# Data_Logger_1.net
KiCad netlist of a schematic drawn in EAGLE
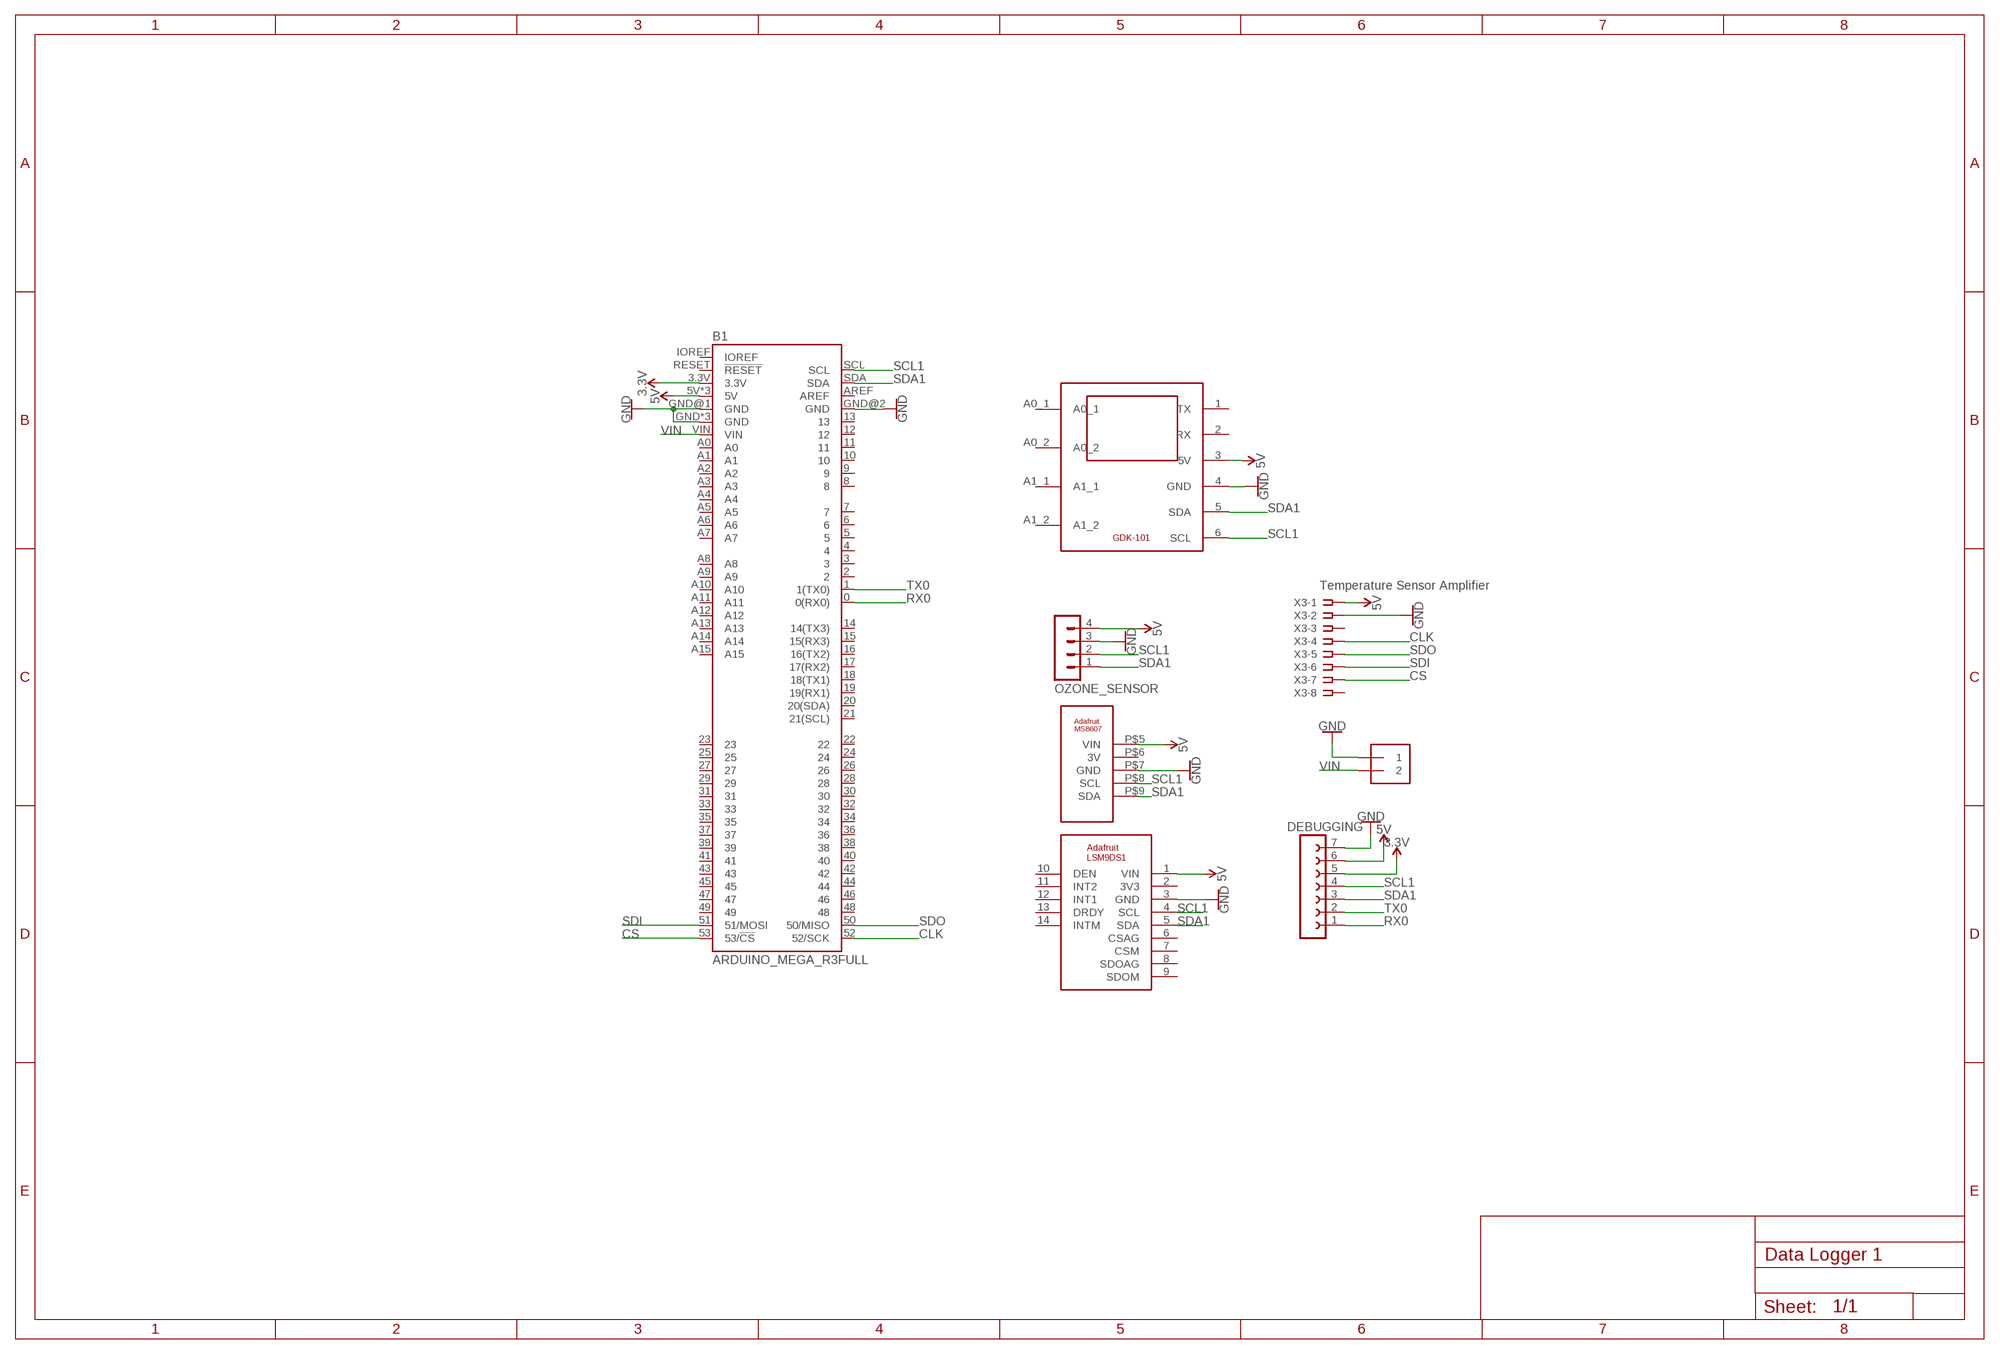
[diagram p0: schematic, sheet 1]

(export (version "E")
  (design (tool "Eeschema 10.0.6"))
  (components
    (comp (ref "B1")
      (value "ARDUINO_MEGA_R3FULL")
      (footprint "eagle-import:ARDUINO_MEGA_NO_SILK")
      (libsource (lib "eagle-import") (part "ARDUINO_MEGA_R3FULL"))
    )
    (comp (ref "DEBUGGING")
      (value "FE07-1")
      (footprint "eagle-import:FE07")
      (libsource (lib "eagle-import") (part "FE07-1"))
    )
    (comp (ref "OZONE_SENSOR")
      (value "OZONE_SENSOR")
      (footprint "eagle-import:MA04-1")
      (libsource (lib "eagle-import") (part "MA04-1"))
    )
    (comp (ref "POWER_7-12V")
      (value "1X2-3.5MM")
      (footprint "eagle-import:1X2-3.5MM")
      (libsource (lib "eagle-import") (part "1X2-3.5MM"))
    )
    (comp (ref "PRESSURE_SENSOR")
      (value "ADAFRUIT_MS8607")
      (footprint "eagle-import:ADAFRUIT_MS8607")
      (libsource (lib "eagle-import") (part "ADAFRUIT_MS8607"))
    )
    (comp (ref "U$1")
      (value "FTLAB_GAMMA_SENSOR_MODULETHROUGH_HOLE")
      (footprint "eagle-import:FTLAB_GAMMA_SENSOR_MODULE")
      (libsource (lib "eagle-import") (part "FTLAB_GAMMA_SENSOR_MODULETHROUGH_HOLE"))
    )
    (comp (ref "U$2")
      (value "ADAFRUIT_LSM9DS1")
      (footprint "eagle-import:ADAFRUIT_LSM9DS1")
      (libsource (lib "eagle-import") (part "ADAFRUIT_LSM9DS1"))
    )
    (comp (ref "X3")
      (value "Temperature Sensor Amplifier")
      (footprint "eagle-import:SSW-108-02-G-S")
      (fields (field (name "MF") "Samtec Inc.") (field (name "MPN") "SSW-108-02-G-S"))
      (libsource (lib "eagle-import") (part "SSW-108-02-G-S"))
    )
  )
  (nets
    (net (code "1") (name "/CLK") (class "Default")
      (node (ref "B1") (pin "52") (pinfunction "52/SCK_52") (pintype "bidirectional"))
      (node (ref "X3") (pin "4") (pinfunction "1_4") (pintype "passive"))
    )
    (net (code "2") (name "/CS") (class "Default")
      (node (ref "B1") (pin "53") (pinfunction "53/~{CS}_53") (pintype "bidirectional"))
      (node (ref "X3") (pin "7") (pinfunction "1_7") (pintype "passive"))
    )
    (net (code "3") (name "/RX0") (class "Default")
      (node (ref "B1") (pin "0") (pinfunction "0(RX0)_0") (pintype "bidirectional"))
      (node (ref "DEBUGGING") (pin "1") (pinfunction "1_1") (pintype "passive"))
    )
    (net (code "4") (name "/SCL1") (class "Default")
      (node (ref "B1") (pin "SCL") (pinfunction "SCL_SCL") (pintype "bidirectional"))
      (node (ref "DEBUGGING") (pin "4") (pinfunction "4_4") (pintype "passive"))
      (node (ref "OZONE_SENSOR") (pin "2") (pinfunction "2_2") (pintype "passive"))
      (node (ref "PRESSURE_SENSOR") (pin "P$8") (pinfunction "SCL_P$8") (pintype "bidirectional"))
      (node (ref "U$1") (pin "6") (pinfunction "SCL_6") (pintype "bidirectional"))
      (node (ref "U$2") (pin "4") (pinfunction "SCL_4") (pintype "bidirectional"))
    )
    (net (code "5") (name "/SDA1") (class "Default")
      (node (ref "B1") (pin "SDA") (pinfunction "SDA_SDA") (pintype "bidirectional"))
      (node (ref "DEBUGGING") (pin "3") (pinfunction "3_3") (pintype "passive"))
      (node (ref "OZONE_SENSOR") (pin "1") (pinfunction "1_1") (pintype "passive"))
      (node (ref "PRESSURE_SENSOR") (pin "P$9") (pinfunction "SDA_P$9") (pintype "bidirectional"))
      (node (ref "U$1") (pin "5") (pinfunction "SDA_5") (pintype "bidirectional"))
      (node (ref "U$2") (pin "5") (pinfunction "SDA_5") (pintype "bidirectional"))
    )
    (net (code "6") (name "/SDI") (class "Default")
      (node (ref "B1") (pin "51") (pinfunction "51/MOSI_51") (pintype "bidirectional"))
      (node (ref "X3") (pin "6") (pinfunction "1_6") (pintype "passive"))
    )
    (net (code "7") (name "/SDO") (class "Default")
      (node (ref "B1") (pin "50") (pinfunction "50/MISO_50") (pintype "bidirectional"))
      (node (ref "X3") (pin "5") (pinfunction "1_5") (pintype "passive"))
    )
    (net (code "8") (name "/TX0") (class "Default")
      (node (ref "B1") (pin "1") (pinfunction "1(TX0)_1") (pintype "bidirectional"))
      (node (ref "DEBUGGING") (pin "2") (pinfunction "2_2") (pintype "passive"))
    )
    (net (code "9") (name "/VIN") (class "Default")
      (node (ref "B1") (pin "VIN") (pinfunction "VIN_VIN") (pintype "bidirectional"))
      (node (ref "POWER_7-12V") (pin "2") (pinfunction "2_2") (pintype "passive"))
    )
    (net (code "10") (name "3.3V") (class "Default")
      (node (ref "B1") (pin "3.3V") (pinfunction "3.3V_3.3V") (pintype "bidirectional"))
      (node (ref "DEBUGGING") (pin "5") (pinfunction "5_5") (pintype "passive"))
    )
    (net (code "11") (name "5V") (class "Default")
      (node (ref "B1") (pin "5V") (pinfunction "5V_5V") (pintype "bidirectional"))
      (node (ref "B1") (pin "5V@1") (pinfunction "5V_5V@1") (pintype "bidirectional"))
      (node (ref "B1") (pin "5V@2") (pinfunction "5V_5V@2") (pintype "bidirectional"))
      (node (ref "DEBUGGING") (pin "6") (pinfunction "6_6") (pintype "passive"))
      (node (ref "OZONE_SENSOR") (pin "4") (pinfunction "4_4") (pintype "passive"))
      (node (ref "PRESSURE_SENSOR") (pin "P$5") (pinfunction "VIN_P$5") (pintype "bidirectional"))
      (node (ref "U$1") (pin "3") (pinfunction "5V_3") (pintype "bidirectional"))
      (node (ref "U$2") (pin "1") (pinfunction "VIN_1") (pintype "bidirectional"))
      (node (ref "X3") (pin "1") (pinfunction "1_1") (pintype "passive"))
    )
    (net (code "12") (name "GND") (class "Default")
      (node (ref "B1") (pin "GND") (pinfunction "GND_GND") (pintype "bidirectional"))
      (node (ref "B1") (pin "GND@1") (pinfunction "GND_GND@1") (pintype "bidirectional"))
      (node (ref "B1") (pin "GND@2") (pinfunction "GND_GND@2") (pintype "bidirectional"))
      (node (ref "B1") (pin "GND@3") (pinfunction "GND_GND@3") (pintype "bidirectional"))
      (node (ref "B1") (pin "GND@4") (pinfunction "GND_GND@4") (pintype "bidirectional"))
      (node (ref "DEBUGGING") (pin "7") (pinfunction "7_7") (pintype "passive"))
      (node (ref "OZONE_SENSOR") (pin "3") (pinfunction "3_3") (pintype "passive"))
      (node (ref "POWER_7-12V") (pin "1") (pinfunction "1_1") (pintype "passive"))
      (node (ref "PRESSURE_SENSOR") (pin "P$7") (pinfunction "GND_P$7") (pintype "bidirectional"))
      (node (ref "U$1") (pin "4") (pinfunction "GND_4") (pintype "bidirectional"))
      (node (ref "U$2") (pin "3") (pinfunction "GND_3") (pintype "bidirectional"))
      (node (ref "X3") (pin "2") (pinfunction "1_2") (pintype "passive"))
    )
    (net (code "13") (name "unconnected-(B1-14(TX3)-Pad14)") (class "Default")
      (node (ref "B1") (pin "14") (pinfunction "14(TX3)_14") (pintype "bidirectional"))
    )
    (net (code "14") (name "unconnected-(B1-15(RX3)-Pad15)") (class "Default")
      (node (ref "B1") (pin "15") (pinfunction "15(RX3)_15") (pintype "bidirectional"))
    )
    (net (code "15") (name "unconnected-(B1-16(TX2)-Pad16)") (class "Default")
      (node (ref "B1") (pin "16") (pinfunction "16(TX2)_16") (pintype "bidirectional"))
    )
    (net (code "16") (name "unconnected-(B1-17(RX2)-Pad17)") (class "Default")
      (node (ref "B1") (pin "17") (pinfunction "17(RX2)_17") (pintype "bidirectional"))
    )
    (net (code "17") (name "unconnected-(B1-18(TX1)-Pad18)") (class "Default")
      (node (ref "B1") (pin "18") (pinfunction "18(TX1)_18") (pintype "bidirectional"))
    )
    (net (code "18") (name "unconnected-(B1-19(RX1)-Pad19)") (class "Default")
      (node (ref "B1") (pin "19") (pinfunction "19(RX1)_19") (pintype "bidirectional"))
    )
    (net (code "19") (name "unconnected-(B1-20(SDA)-Pad20)") (class "Default")
      (node (ref "B1") (pin "20") (pinfunction "20(SDA)_20") (pintype "bidirectional"))
    )
    (net (code "20") (name "unconnected-(B1-21(SCL)-Pad21)") (class "Default")
      (node (ref "B1") (pin "21") (pinfunction "21(SCL)_21") (pintype "bidirectional"))
    )
    (net (code "21") (name "unconnected-(B1-Pad2)") (class "Default")
      (node (ref "B1") (pin "2") (pinfunction "2_2") (pintype "bidirectional"))
    )
    (net (code "22") (name "unconnected-(B1-Pad3)") (class "Default")
      (node (ref "B1") (pin "3") (pinfunction "3_3") (pintype "bidirectional"))
    )
    (net (code "23") (name "unconnected-(B1-Pad4)") (class "Default")
      (node (ref "B1") (pin "4") (pinfunction "4_4") (pintype "bidirectional"))
    )
    (net (code "24") (name "unconnected-(B1-Pad5)") (class "Default")
      (node (ref "B1") (pin "5") (pinfunction "5_5") (pintype "bidirectional"))
    )
    (net (code "25") (name "unconnected-(B1-Pad6)") (class "Default")
      (node (ref "B1") (pin "6") (pinfunction "6_6") (pintype "bidirectional"))
    )
    (net (code "26") (name "unconnected-(B1-Pad7)") (class "Default")
      (node (ref "B1") (pin "7") (pinfunction "7_7") (pintype "bidirectional"))
    )
    (net (code "27") (name "unconnected-(B1-Pad8)") (class "Default")
      (node (ref "B1") (pin "8") (pinfunction "8_8") (pintype "bidirectional"))
    )
    (net (code "28") (name "unconnected-(B1-Pad9)") (class "Default")
      (node (ref "B1") (pin "9") (pinfunction "9_9") (pintype "bidirectional"))
    )
    (net (code "29") (name "unconnected-(B1-Pad10)") (class "Default")
      (node (ref "B1") (pin "10") (pinfunction "10_10") (pintype "bidirectional"))
    )
    (net (code "30") (name "unconnected-(B1-Pad11)") (class "Default")
      (node (ref "B1") (pin "11") (pinfunction "11_11") (pintype "bidirectional"))
    )
    (net (code "31") (name "unconnected-(B1-Pad12)") (class "Default")
      (node (ref "B1") (pin "12") (pinfunction "12_12") (pintype "bidirectional"))
    )
    (net (code "32") (name "unconnected-(B1-Pad13)") (class "Default")
      (node (ref "B1") (pin "13") (pinfunction "13_13") (pintype "bidirectional"))
    )
    (net (code "33") (name "unconnected-(B1-Pad22)") (class "Default")
      (node (ref "B1") (pin "22") (pinfunction "22_22") (pintype "bidirectional"))
    )
    (net (code "34") (name "unconnected-(B1-Pad23)") (class "Default")
      (node (ref "B1") (pin "23") (pinfunction "23_23") (pintype "bidirectional"))
    )
    (net (code "35") (name "unconnected-(B1-Pad24)") (class "Default")
      (node (ref "B1") (pin "24") (pinfunction "24_24") (pintype "bidirectional"))
    )
    (net (code "36") (name "unconnected-(B1-Pad25)") (class "Default")
      (node (ref "B1") (pin "25") (pinfunction "25_25") (pintype "bidirectional"))
    )
    (net (code "37") (name "unconnected-(B1-Pad26)") (class "Default")
      (node (ref "B1") (pin "26") (pinfunction "26_26") (pintype "bidirectional"))
    )
    (net (code "38") (name "unconnected-(B1-Pad27)") (class "Default")
      (node (ref "B1") (pin "27") (pinfunction "27_27") (pintype "bidirectional"))
    )
    (net (code "39") (name "unconnected-(B1-Pad28)") (class "Default")
      (node (ref "B1") (pin "28") (pinfunction "28_28") (pintype "bidirectional"))
    )
    (net (code "40") (name "unconnected-(B1-Pad29)") (class "Default")
      (node (ref "B1") (pin "29") (pinfunction "29_29") (pintype "bidirectional"))
    )
    (net (code "41") (name "unconnected-(B1-Pad30)") (class "Default")
      (node (ref "B1") (pin "30") (pinfunction "30_30") (pintype "bidirectional"))
    )
    (net (code "42") (name "unconnected-(B1-Pad31)") (class "Default")
      (node (ref "B1") (pin "31") (pinfunction "31_31") (pintype "bidirectional"))
    )
    (net (code "43") (name "unconnected-(B1-Pad32)") (class "Default")
      (node (ref "B1") (pin "32") (pinfunction "32_32") (pintype "bidirectional"))
    )
    (net (code "44") (name "unconnected-(B1-Pad33)") (class "Default")
      (node (ref "B1") (pin "33") (pinfunction "33_33") (pintype "bidirectional"))
    )
    (net (code "45") (name "unconnected-(B1-Pad34)") (class "Default")
      (node (ref "B1") (pin "34") (pinfunction "34_34") (pintype "bidirectional"))
    )
    (net (code "46") (name "unconnected-(B1-Pad35)") (class "Default")
      (node (ref "B1") (pin "35") (pinfunction "35_35") (pintype "bidirectional"))
    )
    (net (code "47") (name "unconnected-(B1-Pad36)") (class "Default")
      (node (ref "B1") (pin "36") (pinfunction "36_36") (pintype "bidirectional"))
    )
    (net (code "48") (name "unconnected-(B1-Pad37)") (class "Default")
      (node (ref "B1") (pin "37") (pinfunction "37_37") (pintype "bidirectional"))
    )
    (net (code "49") (name "unconnected-(B1-Pad38)") (class "Default")
      (node (ref "B1") (pin "38") (pinfunction "38_38") (pintype "bidirectional"))
    )
    (net (code "50") (name "unconnected-(B1-Pad39)") (class "Default")
      (node (ref "B1") (pin "39") (pinfunction "39_39") (pintype "bidirectional"))
    )
    (net (code "51") (name "unconnected-(B1-Pad40)") (class "Default")
      (node (ref "B1") (pin "40") (pinfunction "40_40") (pintype "bidirectional"))
    )
    (net (code "52") (name "unconnected-(B1-Pad41)") (class "Default")
      (node (ref "B1") (pin "41") (pinfunction "41_41") (pintype "bidirectional"))
    )
    (net (code "53") (name "unconnected-(B1-Pad42)") (class "Default")
      (node (ref "B1") (pin "42") (pinfunction "42_42") (pintype "bidirectional"))
    )
    (net (code "54") (name "unconnected-(B1-Pad43)") (class "Default")
      (node (ref "B1") (pin "43") (pinfunction "43_43") (pintype "bidirectional"))
    )
    (net (code "55") (name "unconnected-(B1-Pad44)") (class "Default")
      (node (ref "B1") (pin "44") (pinfunction "44_44") (pintype "bidirectional"))
    )
    (net (code "56") (name "unconnected-(B1-Pad45)") (class "Default")
      (node (ref "B1") (pin "45") (pinfunction "45_45") (pintype "bidirectional"))
    )
    (net (code "57") (name "unconnected-(B1-Pad46)") (class "Default")
      (node (ref "B1") (pin "46") (pinfunction "46_46") (pintype "bidirectional"))
    )
    (net (code "58") (name "unconnected-(B1-Pad47)") (class "Default")
      (node (ref "B1") (pin "47") (pinfunction "47_47") (pintype "bidirectional"))
    )
    (net (code "59") (name "unconnected-(B1-Pad48)") (class "Default")
      (node (ref "B1") (pin "48") (pinfunction "48_48") (pintype "bidirectional"))
    )
    (net (code "60") (name "unconnected-(B1-Pad49)") (class "Default")
      (node (ref "B1") (pin "49") (pinfunction "49_49") (pintype "bidirectional"))
    )
    (net (code "61") (name "unconnected-(B1-PadA0)") (class "Default")
      (node (ref "B1") (pin "A0") (pinfunction "A0_A0") (pintype "bidirectional"))
    )
    (net (code "62") (name "unconnected-(B1-PadA1)") (class "Default")
      (node (ref "B1") (pin "A1") (pinfunction "A1_A1") (pintype "bidirectional"))
    )
    (net (code "63") (name "unconnected-(B1-PadA2)") (class "Default")
      (node (ref "B1") (pin "A2") (pinfunction "A2_A2") (pintype "bidirectional"))
    )
    (net (code "64") (name "unconnected-(B1-PadA3)") (class "Default")
      (node (ref "B1") (pin "A3") (pinfunction "A3_A3") (pintype "bidirectional"))
    )
    (net (code "65") (name "unconnected-(B1-PadA4)") (class "Default")
      (node (ref "B1") (pin "A4") (pinfunction "A4_A4") (pintype "bidirectional"))
    )
    (net (code "66") (name "unconnected-(B1-PadA5)") (class "Default")
      (node (ref "B1") (pin "A5") (pinfunction "A5_A5") (pintype "bidirectional"))
    )
    (net (code "67") (name "unconnected-(B1-PadA6)") (class "Default")
      (node (ref "B1") (pin "A6") (pinfunction "A6_A6") (pintype "bidirectional"))
    )
    (net (code "68") (name "unconnected-(B1-PadA7)") (class "Default")
      (node (ref "B1") (pin "A7") (pinfunction "A7_A7") (pintype "bidirectional"))
    )
    (net (code "69") (name "unconnected-(B1-PadA8)") (class "Default")
      (node (ref "B1") (pin "A8") (pinfunction "A8_A8") (pintype "bidirectional"))
    )
    (net (code "70") (name "unconnected-(B1-PadA9)") (class "Default")
      (node (ref "B1") (pin "A9") (pinfunction "A9_A9") (pintype "bidirectional"))
    )
    (net (code "71") (name "unconnected-(B1-PadA10)") (class "Default")
      (node (ref "B1") (pin "A10") (pinfunction "A10_A10") (pintype "bidirectional"))
    )
    (net (code "72") (name "unconnected-(B1-PadA11)") (class "Default")
      (node (ref "B1") (pin "A11") (pinfunction "A11_A11") (pintype "bidirectional"))
    )
    (net (code "73") (name "unconnected-(B1-PadA12)") (class "Default")
      (node (ref "B1") (pin "A12") (pinfunction "A12_A12") (pintype "bidirectional"))
    )
    (net (code "74") (name "unconnected-(B1-PadA13)") (class "Default")
      (node (ref "B1") (pin "A13") (pinfunction "A13_A13") (pintype "bidirectional"))
    )
    (net (code "75") (name "unconnected-(B1-PadA14)") (class "Default")
      (node (ref "B1") (pin "A14") (pinfunction "A14_A14") (pintype "bidirectional"))
    )
    (net (code "76") (name "unconnected-(B1-PadA15)") (class "Default")
      (node (ref "B1") (pin "A15") (pinfunction "A15_A15") (pintype "bidirectional"))
    )
    (net (code "77") (name "unconnected-(B1-PadAREF)") (class "Default")
      (node (ref "B1") (pin "AREF") (pinfunction "AREF_AREF") (pintype "bidirectional"))
    )
    (net (code "78") (name "unconnected-(B1-PadIOREF)") (class "Default")
      (node (ref "B1") (pin "IOREF") (pinfunction "IOREF_IOREF") (pintype "bidirectional"))
    )
    (net (code "79") (name "unconnected-(B1-~{RESET}-PadRESET)") (class "Default")
      (node (ref "B1") (pin "RESET") (pinfunction "~{RESET}_RESET") (pintype "bidirectional"))
    )
    (net (code "80") (name "unconnected-(PRESSURE_SENSOR-3V-PadP$6)") (class "Default")
      (node (ref "PRESSURE_SENSOR") (pin "P$6") (pinfunction "3V_P$6") (pintype "bidirectional"))
    )
    (net (code "81") (name "unconnected-(U$1-PadA0_1)") (class "Default")
      (node (ref "U$1") (pin "A0_1") (pinfunction "A0_1_A0_1") (pintype "bidirectional"))
    )
    (net (code "82") (name "unconnected-(U$1-PadA0_2)") (class "Default")
      (node (ref "U$1") (pin "A0_2") (pinfunction "A0_2_A0_2") (pintype "bidirectional"))
    )
    (net (code "83") (name "unconnected-(U$1-PadA1_1)") (class "Default")
      (node (ref "U$1") (pin "A1_1") (pinfunction "A1_1_A1_1") (pintype "bidirectional"))
    )
    (net (code "84") (name "unconnected-(U$1-PadA1_2)") (class "Default")
      (node (ref "U$1") (pin "A1_2") (pinfunction "A1_2_A1_2") (pintype "bidirectional"))
    )
    (net (code "85") (name "unconnected-(U$1-RX-Pad2)") (class "Default")
      (node (ref "U$1") (pin "2") (pinfunction "RX_2") (pintype "bidirectional"))
    )
    (net (code "86") (name "unconnected-(U$1-TX-Pad1)") (class "Default")
      (node (ref "U$1") (pin "1") (pinfunction "TX_1") (pintype "bidirectional"))
    )
    (net (code "87") (name "unconnected-(U$2-3V3-Pad2)") (class "Default")
      (node (ref "U$2") (pin "2") (pinfunction "3V3_2") (pintype "bidirectional"))
    )
    (net (code "88") (name "unconnected-(U$2-CSAG-Pad6)") (class "Default")
      (node (ref "U$2") (pin "6") (pinfunction "CSAG_6") (pintype "bidirectional"))
    )
    (net (code "89") (name "unconnected-(U$2-CSM-Pad7)") (class "Default")
      (node (ref "U$2") (pin "7") (pinfunction "CSM_7") (pintype "bidirectional"))
    )
    (net (code "90") (name "unconnected-(U$2-DEN-Pad10)") (class "Default")
      (node (ref "U$2") (pin "10") (pinfunction "DEN_10") (pintype "bidirectional"))
    )
    (net (code "91") (name "unconnected-(U$2-DRDY-Pad13)") (class "Default")
      (node (ref "U$2") (pin "13") (pinfunction "DRDY_13") (pintype "bidirectional"))
    )
    (net (code "92") (name "unconnected-(U$2-INT1-Pad12)") (class "Default")
      (node (ref "U$2") (pin "12") (pinfunction "INT1_12") (pintype "bidirectional"))
    )
    (net (code "93") (name "unconnected-(U$2-INT2-Pad11)") (class "Default")
      (node (ref "U$2") (pin "11") (pinfunction "INT2_11") (pintype "bidirectional"))
    )
    (net (code "94") (name "unconnected-(U$2-INTM-Pad14)") (class "Default")
      (node (ref "U$2") (pin "14") (pinfunction "INTM_14") (pintype "bidirectional"))
    )
    (net (code "95") (name "unconnected-(U$2-SDOAG-Pad8)") (class "Default")
      (node (ref "U$2") (pin "8") (pinfunction "SDOAG_8") (pintype "bidirectional"))
    )
    (net (code "96") (name "unconnected-(U$2-SDOM-Pad9)") (class "Default")
      (node (ref "U$2") (pin "9") (pinfunction "SDOM_9") (pintype "bidirectional"))
    )
    (net (code "97") (name "unconnected-(X3C-1-Pad3)") (class "Default")
      (node (ref "X3") (pin "3") (pinfunction "1_3") (pintype "passive"))
    )
    (net (code "98") (name "unconnected-(X3H-1-Pad8)") (class "Default")
      (node (ref "X3") (pin "8") (pinfunction "1_8") (pintype "passive"))
    )
  )
)
